# FT231X.net
KiCad netlist of a schematic drawn in EAGLE
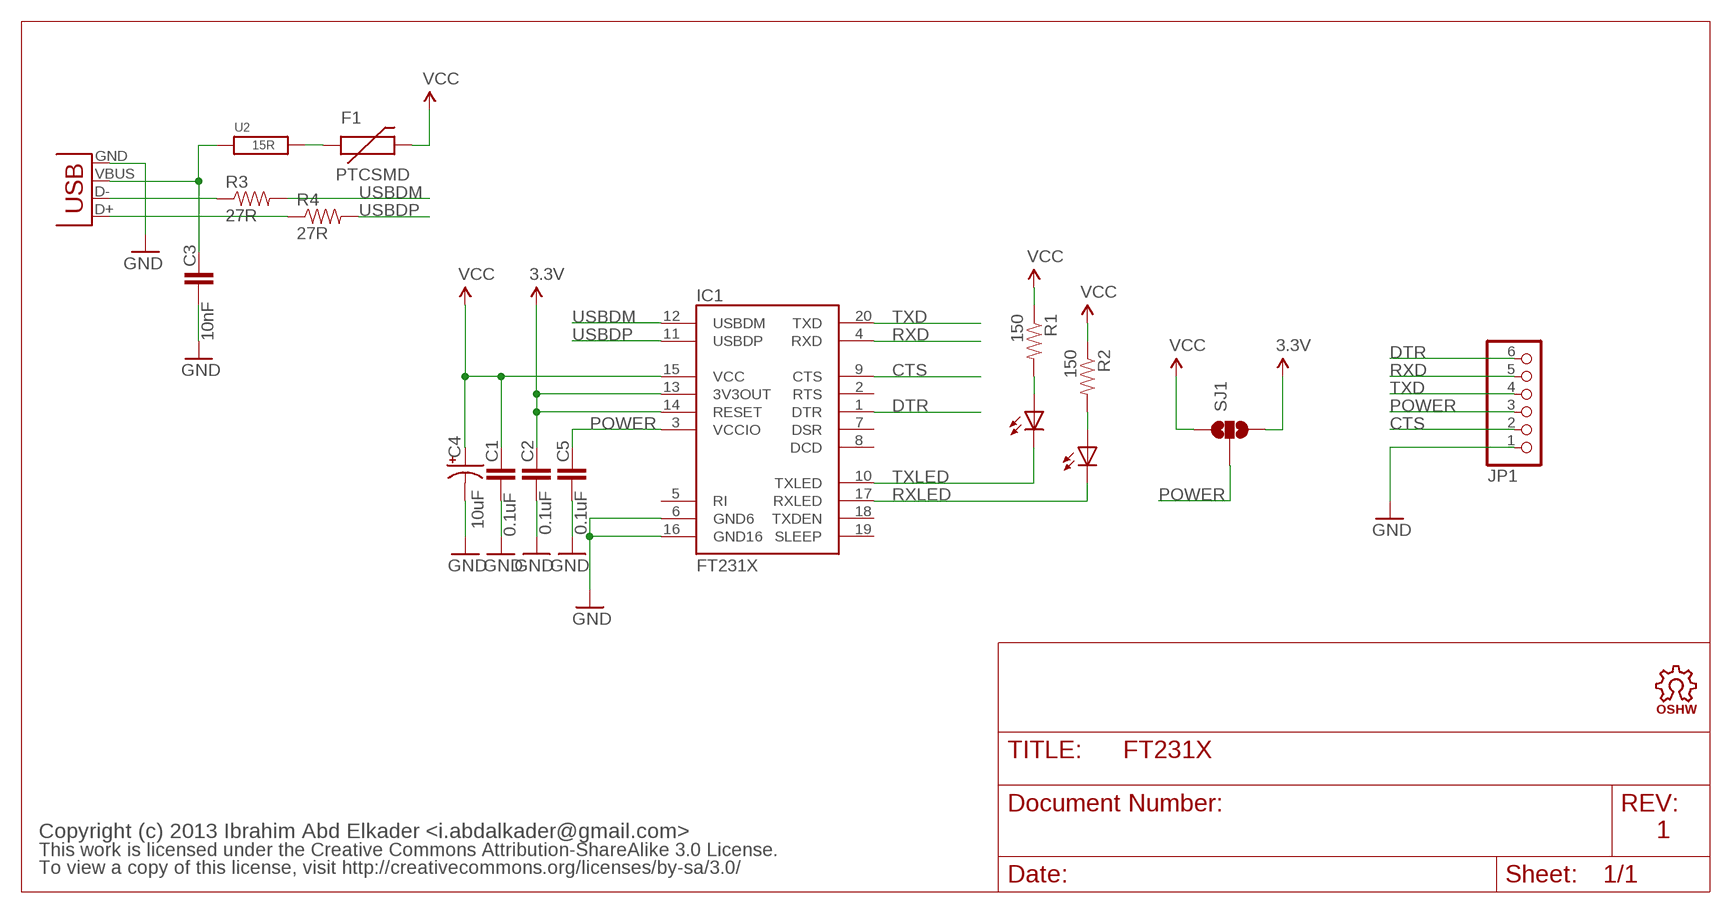
[diagram p0: schematic, sheet 1]

(export (version "E")
  (design (tool "Eeschema 10.0.6"))
  (components
    (comp (ref "C1")
      (value "0.1uF")
      (footprint "eagle-import:0402-CAP")
      (libsource (lib "eagle-import") (part "CAP0402-CAP"))
    )
    (comp (ref "C2")
      (value "0.1uF")
      (footprint "eagle-import:0402-CAP")
      (libsource (lib "eagle-import") (part "CAP0402-CAP"))
    )
    (comp (ref "C3")
      (value "10nF")
      (footprint "eagle-import:0402-CAP")
      (libsource (lib "eagle-import") (part "CAP0402-CAP"))
    )
    (comp (ref "C4")
      (value "10uF")
      (footprint "eagle-import:EIA3216")
      (libsource (lib "eagle-import") (part "CAP_POL1206"))
    )
    (comp (ref "C5")
      (value "0.1uF")
      (footprint "eagle-import:0402-CAP")
      (libsource (lib "eagle-import") (part "CAP0402-CAP"))
    )
    (comp (ref "D1")
      (value "LED0603")
      (footprint "eagle-import:LED-0603")
      (libsource (lib "eagle-import") (part "LED0603"))
    )
    (comp (ref "D2")
      (value "LED0603")
      (footprint "eagle-import:LED-0603")
      (libsource (lib "eagle-import") (part "LED0603"))
    )
    (comp (ref "F1")
      (value "PTCSMD")
      (footprint "eagle-import:PTC-1206")
      (libsource (lib "eagle-import") (part "PTCSMD"))
    )
    (comp (ref "IC1")
      (value "FT231X")
      (footprint "eagle-import:SSOP20")
      (libsource (lib "eagle-import") (part "FT231X"))
    )
    (comp (ref "JP1")
      (value "PINHD-1X6")
      (footprint "eagle-import:1X06")
      (libsource (lib "eagle-import") (part "PINHD-1X6"))
    )
    (comp (ref "LOGO1")
      (value "OSHW_LOGO_FILLX0100-NT")
      (footprint "eagle-import:OSHW_FILLX100_NOTEXT")
      (libsource (lib "eagle-import") (part "OSHW_LOGO_FILLX0100-NT"))
    )
    (comp (ref "R1")
      (value "150")
      (footprint "eagle-import:0402-RES")
      (libsource (lib "eagle-import") (part "RESISTOR0402-RES"))
    )
    (comp (ref "R2")
      (value "150")
      (footprint "eagle-import:0402-RES")
      (libsource (lib "eagle-import") (part "RESISTOR0402-RES"))
    )
    (comp (ref "R3")
      (value "27R")
      (footprint "eagle-import:0402-RES")
      (libsource (lib "eagle-import") (part "RESISTOR0402-RES"))
    )
    (comp (ref "R4")
      (value "27R")
      (footprint "eagle-import:0402-RES")
      (libsource (lib "eagle-import") (part "RESISTOR0402-RES"))
    )
    (comp (ref "SJ1")
      (value "SOLDERJUMPER_2WAYS")
      (footprint "eagle-import:SJ_3")
      (libsource (lib "eagle-import") (part "SOLDERJUMPER_2WAYS"))
    )
    (comp (ref "U2")
      (value "15R")
      (footprint "eagle-import:0402-CAP")
      (libsource (lib "eagle-import") (part "BEAD"))
    )
    (comp (ref "X1")
      (value "USBSMD")
      (footprint "eagle-import:USB-MINIB")
      (libsource (lib "eagle-import") (part "USBSMD"))
    )
  )
  (nets
    (net (code "1") (name "/CTS") (class "Default")
      (node (ref "IC1") (pin "9") (pinfunction "CTS_9") (pintype "input"))
      (node (ref "JP1") (pin "2") (pinfunction "2_2") (pintype "passive"))
    )
    (net (code "2") (name "/DTR") (class "Default")
      (node (ref "IC1") (pin "1") (pinfunction "DTR_1") (pintype "output"))
      (node (ref "JP1") (pin "6") (pinfunction "6_6") (pintype "passive"))
    )
    (net (code "3") (name "/POWER") (class "Default")
      (node (ref "C5") (pin "1") (pinfunction "1_1") (pintype "passive"))
      (node (ref "IC1") (pin "3") (pinfunction "VCCIO_3") (pintype "power_in"))
      (node (ref "JP1") (pin "3") (pinfunction "3_3") (pintype "passive"))
      (node (ref "SJ1") (pin "2") (pinfunction "2_2") (pintype "passive"))
    )
    (net (code "4") (name "/RXD") (class "Default")
      (node (ref "IC1") (pin "4") (pinfunction "RXD_4") (pintype "input"))
      (node (ref "JP1") (pin "5") (pinfunction "5_5") (pintype "passive"))
    )
    (net (code "5") (name "/RXLED") (class "Default")
      (node (ref "D1") (pin "C") (pinfunction "C_C") (pintype "passive"))
      (node (ref "IC1") (pin "17") (pinfunction "RXLED_17") (pintype "input"))
    )
    (net (code "6") (name "/TXD") (class "Default")
      (node (ref "IC1") (pin "20") (pinfunction "TXD_20") (pintype "output"))
      (node (ref "JP1") (pin "4") (pinfunction "4_4") (pintype "passive"))
    )
    (net (code "7") (name "/TXLED") (class "Default")
      (node (ref "D2") (pin "C") (pinfunction "C_C") (pintype "passive"))
      (node (ref "IC1") (pin "10") (pinfunction "TXLED_10") (pintype "input"))
    )
    (net (code "8") (name "/USBDM") (class "Default")
      (node (ref "IC1") (pin "12") (pinfunction "USBDM_12") (pintype "bidirectional"))
      (node (ref "R3") (pin "2") (pinfunction "2_2") (pintype "passive"))
    )
    (net (code "9") (name "/USBDP") (class "Default")
      (node (ref "IC1") (pin "11") (pinfunction "USBDP_11") (pintype "bidirectional"))
      (node (ref "R4") (pin "2") (pinfunction "2_2") (pintype "passive"))
    )
    (net (code "10") (name "3.3V") (class "Default")
      (node (ref "C2") (pin "1") (pinfunction "1_1") (pintype "passive"))
      (node (ref "IC1") (pin "13") (pinfunction "3V3OUT_13") (pintype "output"))
      (node (ref "IC1") (pin "14") (pinfunction "RESET_14") (pintype "input"))
      (node (ref "SJ1") (pin "3") (pinfunction "3_3") (pintype "passive"))
    )
    (net (code "11") (name "GND") (class "Default")
      (node (ref "C1") (pin "2") (pinfunction "2_2") (pintype "passive"))
      (node (ref "C2") (pin "2") (pinfunction "2_2") (pintype "passive"))
      (node (ref "C3") (pin "2") (pinfunction "2_2") (pintype "passive"))
      (node (ref "C4") (pin "C") (pinfunction "-_C") (pintype "passive"))
      (node (ref "C5") (pin "2") (pinfunction "2_2") (pintype "passive"))
      (node (ref "IC1") (pin "16") (pinfunction "GND16_16") (pintype "power_in"))
      (node (ref "IC1") (pin "6") (pinfunction "GND6_6") (pintype "power_in"))
      (node (ref "JP1") (pin "1") (pinfunction "1_1") (pintype "passive"))
      (node (ref "X1") (pin "GND") (pinfunction "GND_GND") (pintype "bidirectional"))
    )
    (net (code "12") (name "Net-(C3-Pad1)") (class "Default")
      (node (ref "C3") (pin "1") (pinfunction "1_1") (pintype "passive"))
      (node (ref "U2") (pin "1") (pinfunction "1_1") (pintype "passive"))
      (node (ref "X1") (pin "VBUS") (pinfunction "VBUS_VBUS") (pintype "bidirectional"))
    )
    (net (code "13") (name "Net-(D1-PadA)") (class "Default")
      (node (ref "D1") (pin "A") (pinfunction "A_A") (pintype "passive"))
      (node (ref "R2") (pin "2") (pinfunction "2_2") (pintype "passive"))
    )
    (net (code "14") (name "Net-(D2-PadA)") (class "Default")
      (node (ref "D2") (pin "A") (pinfunction "A_A") (pintype "passive"))
      (node (ref "R1") (pin "2") (pinfunction "2_2") (pintype "passive"))
    )
    (net (code "15") (name "Net-(F1-Pad1)") (class "Default")
      (node (ref "F1") (pin "1") (pinfunction "1_1") (pintype "bidirectional"))
      (node (ref "U2") (pin "2") (pinfunction "2_2") (pintype "passive"))
    )
    (net (code "16") (name "Net-(R3-Pad1)") (class "Default")
      (node (ref "R3") (pin "1") (pinfunction "1_1") (pintype "passive"))
      (node (ref "X1") (pin "D-") (pinfunction "D-_D-") (pintype "bidirectional"))
    )
    (net (code "17") (name "Net-(R4-Pad1)") (class "Default")
      (node (ref "R4") (pin "1") (pinfunction "1_1") (pintype "passive"))
      (node (ref "X1") (pin "D+") (pinfunction "D+_D+") (pintype "bidirectional"))
    )
    (net (code "18") (name "VCC") (class "Default")
      (node (ref "C1") (pin "1") (pinfunction "1_1") (pintype "passive"))
      (node (ref "C4") (pin "A") (pinfunction "+_A") (pintype "passive"))
      (node (ref "F1") (pin "2") (pinfunction "2_2") (pintype "bidirectional"))
      (node (ref "IC1") (pin "15") (pinfunction "VCC_15") (pintype "power_in"))
      (node (ref "R1") (pin "1") (pinfunction "1_1") (pintype "passive"))
      (node (ref "R2") (pin "1") (pinfunction "1_1") (pintype "passive"))
      (node (ref "SJ1") (pin "1") (pinfunction "1_1") (pintype "passive"))
    )
    (net (code "19") (name "unconnected-(IC1-DCD-Pad8)") (class "Default")
      (node (ref "IC1") (pin "8") (pinfunction "DCD_8") (pintype "input"))
    )
    (net (code "20") (name "unconnected-(IC1-DSR-Pad7)") (class "Default")
      (node (ref "IC1") (pin "7") (pinfunction "DSR_7") (pintype "input"))
    )
    (net (code "21") (name "unconnected-(IC1-RI-Pad5)") (class "Default")
      (node (ref "IC1") (pin "5") (pinfunction "RI_5") (pintype "input"))
    )
    (net (code "22") (name "unconnected-(IC1-RTS-Pad2)") (class "Default")
      (node (ref "IC1") (pin "2") (pinfunction "RTS_2") (pintype "output"))
    )
    (net (code "23") (name "unconnected-(IC1-SLEEP-Pad19)") (class "Default")
      (node (ref "IC1") (pin "19") (pinfunction "SLEEP_19") (pintype "input"))
    )
    (net (code "24") (name "unconnected-(IC1-TXDEN-Pad18)") (class "Default")
      (node (ref "IC1") (pin "18") (pinfunction "TXDEN_18") (pintype "input"))
    )
  )
)
